# LVDS_IFC_MCX.net
KiCad netlist of a schematic drawn in Altium Designer
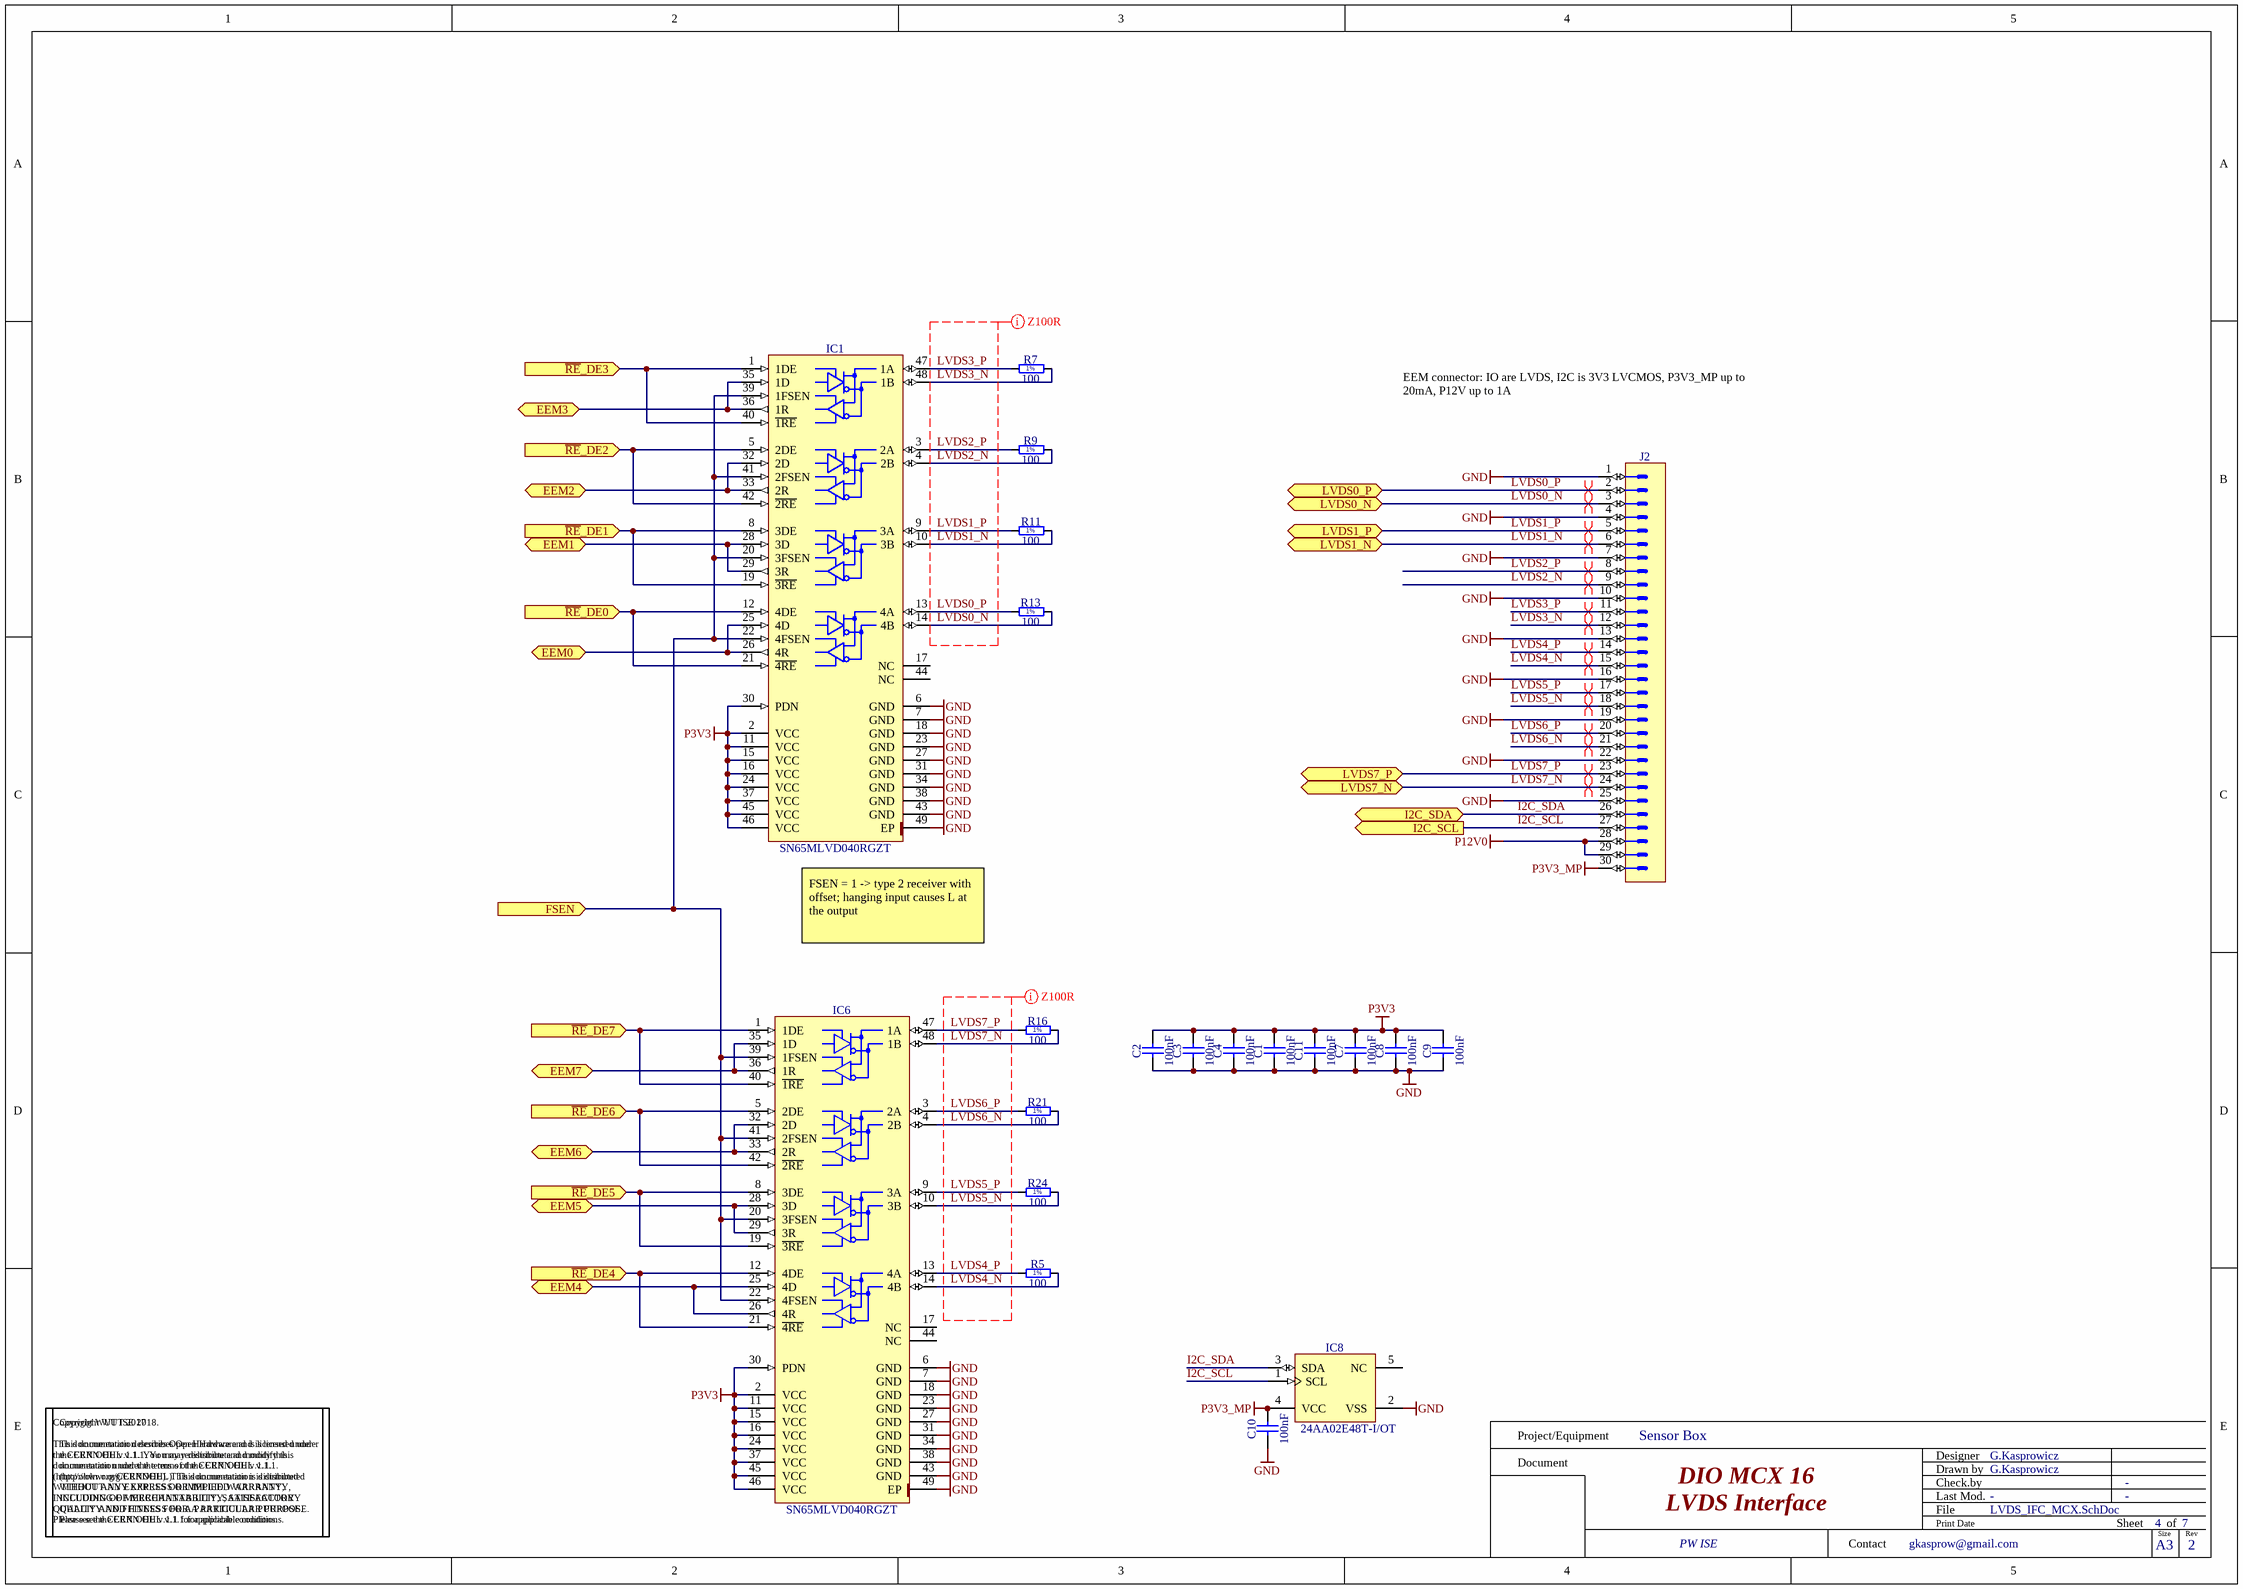
[diagram p0: LVDS_IFC_MCX.SchDoc]

(export (version "E")
  (design (tool "Eeschema 10.0.6"))
  (components
    (comp (ref "C1")
      (value "100nF")
      (footprint "CAPC1005X55N")
      (description "Non-polarised capacitor")
      (fields
        (field (name "PART NUMBER") "CC0402_100NF_16V_10%_X5R")
        (field (name "VOLTAGE") "16V")
        (field (name "AUTHOR") "CERN DEM JLC")
      )
      (libsource (lib "Capacitors") (part "Capacitor - non polarized"))
    )
    (comp (ref "C2")
      (value "100nF")
      (footprint "CAPC1005X55N")
      (description "Non-polarised capacitor")
      (fields
        (field (name "PART NUMBER") "CC0402_100NF_16V_10%_X5R")
        (field (name "VOLTAGE") "16V")
        (field (name "AUTHOR") "CERN DEM JLC")
      )
      (libsource (lib "Capacitors") (part "Capacitor - non polarized"))
    )
    (comp (ref "C3")
      (value "100nF")
      (footprint "CAPC1005X55N")
      (description "Non-polarised capacitor")
      (fields
        (field (name "PART NUMBER") "CC0402_100NF_16V_10%_X5R")
        (field (name "VOLTAGE") "16V")
        (field (name "AUTHOR") "CERN DEM JLC")
      )
      (libsource (lib "Capacitors") (part "Capacitor - non polarized"))
    )
    (comp (ref "C4")
      (value "100nF")
      (footprint "CAPC1005X55N")
      (description "Non-polarised capacitor")
      (fields
        (field (name "PART NUMBER") "CC0402_100NF_16V_10%_X5R")
        (field (name "VOLTAGE") "16V")
        (field (name "AUTHOR") "CERN DEM JLC")
      )
      (libsource (lib "Capacitors") (part "Capacitor - non polarized"))
    )
    (comp (ref "C7")
      (value "100nF")
      (footprint "CAPC1005X55N")
      (description "Non-polarised capacitor")
      (fields
        (field (name "PART NUMBER") "CC0402_100NF_16V_10%_X5R")
        (field (name "VOLTAGE") "16V")
        (field (name "AUTHOR") "CERN DEM JLC")
      )
      (libsource (lib "Capacitors") (part "Capacitor - non polarized"))
    )
    (comp (ref "C8")
      (value "100nF")
      (footprint "CAPC1005X55N")
      (description "Non-polarised capacitor")
      (fields
        (field (name "PART NUMBER") "CC0402_100NF_16V_10%_X5R")
        (field (name "VOLTAGE") "16V")
        (field (name "AUTHOR") "CERN DEM JLC")
      )
      (libsource (lib "Capacitors") (part "Capacitor - non polarized"))
    )
    (comp (ref "C9")
      (value "100nF")
      (footprint "CAPC1005X55N")
      (description "Non-polarised capacitor")
      (fields
        (field (name "PART NUMBER") "CC0402_100NF_16V_10%_X5R")
        (field (name "VOLTAGE") "16V")
        (field (name "AUTHOR") "CERN DEM JLC")
      )
      (libsource (lib "Capacitors") (part "Capacitor - non polarized"))
    )
    (comp (ref "C10")
      (value "100nF")
      (footprint "CAPC1005X55N")
      (description "Non-polarised capacitor")
      (fields
        (field (name "PART NUMBER") "CC0402_100NF_16V_10%_X5R")
        (field (name "VOLTAGE") "16V")
        (field (name "AUTHOR") "CERN DEM JLC")
      )
      (libsource (lib "Capacitors") (part "Capacitor - non polarized"))
    )
    (comp (ref "C11")
      (value "100nF")
      (footprint "CAPC1005X55N")
      (description "Non-polarised capacitor")
      (fields
        (field (name "PART NUMBER") "CC0402_100NF_16V_10%_X5R")
        (field (name "VOLTAGE") "16V")
        (field (name "AUTHOR") "CERN DEM JLC")
      )
      (libsource (lib "Capacitors") (part "Capacitor - non polarized"))
    )
    (comp (ref "IC1")
      (value "SN65MLVD040RGZT")
      (footprint "QFN50P700X700X100-49N-S420")
      (description "4-Channel Half-Duplex M-LVDS Line Transceiver")
      (fields (field (name "MANUFACTURER") "TEXAS INSTRUMENTS") (field (name "AUTHOR") "CERN DEM JLC"))
      (libsource (lib "ICs And Semiconductors") (part "SN65MLVD040"))
    )
    (comp (ref "IC6")
      (value "SN65MLVD040RGZT")
      (footprint "QFN50P700X700X100-49N-S420")
      (description "4-Channel Half-Duplex M-LVDS Line Transceiver")
      (fields (field (name "MANUFACTURER") "TEXAS INSTRUMENTS") (field (name "AUTHOR") "CERN DEM JLC"))
      (libsource (lib "ICs And Semiconductors") (part "SN65MLVD040"))
    )
    (comp (ref "IC8")
      (value "24AA02E48T-I/OT")
      (footprint "SOT95P280X145-5N")
      (description "1.7V-5.5V, 2K I2C Serial EEPROM With EUI-48 Node Identity")
      (fields (field (name "MANUFACTURER") "MICROCHIP TECHNOLOGY") (field (name "AUTHOR") "CERN DEM MR"))
      (libsource (lib "ICs And Semiconductors") (part "24AA02E48T-I/OT"))
    )
    (comp (ref "J2")
      (value "~")
      (footprint "3M_N2530-6002RB")
      (description "Connector 30 Male")
      (fields
        (field (name "PART NUMBER") "3M_N2530-6002RB")
        (field (name "MANUFACTURER") "3M")
        (field (name "AUTHOR") "CERN DEM JLC")
      )
      (libsource (lib "Connectors") (part "Connector 30 Male"))
    )
    (comp (ref "R5")
      (value "100")
      (footprint "RESC1005X40N")
      (description "Resistor - 1%")
      (fields
        (field (name "PART NUMBER") "R0402_100R_1%_0.1W_100PPM")
        (field (name "POWER") "0.1W")
        (field (name "AUTHOR") "CERN DEM JLC")
      )
      (libsource (lib "Resistors") (part "Resistor - 1%"))
    )
    (comp (ref "R7")
      (value "100")
      (footprint "RESC1005X40N")
      (description "Resistor - 1%")
      (fields
        (field (name "PART NUMBER") "R0402_100R_1%_0.1W_100PPM")
        (field (name "POWER") "0.1W")
        (field (name "AUTHOR") "CERN DEM JLC")
      )
      (libsource (lib "Resistors") (part "Resistor - 1%"))
    )
    (comp (ref "R9")
      (value "100")
      (footprint "RESC1005X40N")
      (description "Resistor - 1%")
      (fields
        (field (name "PART NUMBER") "R0402_100R_1%_0.1W_100PPM")
        (field (name "POWER") "0.1W")
        (field (name "AUTHOR") "CERN DEM JLC")
      )
      (libsource (lib "Resistors") (part "Resistor - 1%"))
    )
    (comp (ref "R11")
      (value "100")
      (footprint "RESC1005X40N")
      (description "Resistor - 1%")
      (fields
        (field (name "PART NUMBER") "R0402_100R_1%_0.1W_100PPM")
        (field (name "POWER") "0.1W")
        (field (name "AUTHOR") "CERN DEM JLC")
      )
      (libsource (lib "Resistors") (part "Resistor - 1%"))
    )
    (comp (ref "R13")
      (value "100")
      (footprint "RESC1005X40N")
      (description "Resistor - 1%")
      (fields
        (field (name "PART NUMBER") "R0402_100R_1%_0.1W_100PPM")
        (field (name "POWER") "0.1W")
        (field (name "AUTHOR") "CERN DEM JLC")
      )
      (libsource (lib "Resistors") (part "Resistor - 1%"))
    )
    (comp (ref "R16")
      (value "100")
      (footprint "RESC1005X40N")
      (description "Resistor - 1%")
      (fields
        (field (name "PART NUMBER") "R0402_100R_1%_0.1W_100PPM")
        (field (name "POWER") "0.1W")
        (field (name "AUTHOR") "CERN DEM JLC")
      )
      (libsource (lib "Resistors") (part "Resistor - 1%"))
    )
    (comp (ref "R21")
      (value "100")
      (footprint "RESC1005X40N")
      (description "Resistor - 1%")
      (fields
        (field (name "PART NUMBER") "R0402_100R_1%_0.1W_100PPM")
        (field (name "POWER") "0.1W")
        (field (name "AUTHOR") "CERN DEM JLC")
      )
      (libsource (lib "Resistors") (part "Resistor - 1%"))
    )
    (comp (ref "R24")
      (value "100")
      (footprint "RESC1005X40N")
      (description "Resistor - 1%")
      (fields
        (field (name "PART NUMBER") "R0402_100R_1%_0.1W_100PPM")
        (field (name "POWER") "0.1W")
        (field (name "AUTHOR") "CERN DEM JLC")
      )
      (libsource (lib "Resistors") (part "Resistor - 1%"))
    )
  )
  (nets
    (net (code "1") (name "/EEM0") (class "Default")
      (node (ref "IC1") (pin "25") (pinfunction "4D_25") (pintype "input"))
      (node (ref "IC1") (pin "26") (pinfunction "4R_26") (pintype "output"))
    )
    (net (code "2") (name "/EEM1") (class "Default")
      (node (ref "IC1") (pin "28") (pinfunction "3D_28") (pintype "input"))
      (node (ref "IC1") (pin "29") (pinfunction "3R_29") (pintype "output"))
    )
    (net (code "3") (name "/EEM2") (class "Default")
      (node (ref "IC1") (pin "32") (pinfunction "2D_32") (pintype "input"))
      (node (ref "IC1") (pin "33") (pinfunction "2R_33") (pintype "output"))
    )
    (net (code "4") (name "/EEM3") (class "Default")
      (node (ref "IC1") (pin "35") (pinfunction "1D_35") (pintype "input"))
      (node (ref "IC1") (pin "36") (pinfunction "1R_36") (pintype "output"))
    )
    (net (code "5") (name "/EEM4") (class "Default")
      (node (ref "IC6") (pin "25") (pinfunction "4D_25") (pintype "input"))
      (node (ref "IC6") (pin "26") (pinfunction "4R_26") (pintype "output"))
    )
    (net (code "6") (name "/EEM5") (class "Default")
      (node (ref "IC6") (pin "28") (pinfunction "3D_28") (pintype "input"))
      (node (ref "IC6") (pin "29") (pinfunction "3R_29") (pintype "output"))
    )
    (net (code "7") (name "/EEM6") (class "Default")
      (node (ref "IC6") (pin "32") (pinfunction "2D_32") (pintype "input"))
      (node (ref "IC6") (pin "33") (pinfunction "2R_33") (pintype "output"))
    )
    (net (code "8") (name "/EEM7") (class "Default")
      (node (ref "IC6") (pin "35") (pinfunction "1D_35") (pintype "input"))
      (node (ref "IC6") (pin "36") (pinfunction "1R_36") (pintype "output"))
    )
    (net (code "9") (name "/FSEN") (class "Default")
      (node (ref "IC1") (pin "20") (pinfunction "3FSEN_20") (pintype "input"))
      (node (ref "IC1") (pin "22") (pinfunction "4FSEN_22") (pintype "input"))
      (node (ref "IC1") (pin "39") (pinfunction "1FSEN_39") (pintype "input"))
      (node (ref "IC1") (pin "41") (pinfunction "2FSEN_41") (pintype "input"))
      (node (ref "IC6") (pin "20") (pinfunction "3FSEN_20") (pintype "input"))
      (node (ref "IC6") (pin "22") (pinfunction "4FSEN_22") (pintype "input"))
      (node (ref "IC6") (pin "39") (pinfunction "1FSEN_39") (pintype "input"))
      (node (ref "IC6") (pin "41") (pinfunction "2FSEN_41") (pintype "input"))
    )
    (net (code "10") (name "/I2C_SCL") (class "Default")
      (node (ref "IC8") (pin "1") (pinfunction "SCL_1") (pintype "input"))
      (node (ref "J2") (pin "27") (pinfunction "27_27") (pintype "bidirectional"))
    )
    (net (code "11") (name "/I2C_SDA") (class "Default")
      (node (ref "IC8") (pin "3") (pinfunction "SDA_3") (pintype "bidirectional"))
      (node (ref "J2") (pin "26") (pinfunction "26_26") (pintype "bidirectional"))
    )
    (net (code "12") (name "/LVDS0_N") (class "Default")
      (node (ref "IC1") (pin "14") (pinfunction "4B_14") (pintype "bidirectional"))
      (node (ref "J2") (pin "3") (pinfunction "3_3") (pintype "bidirectional"))
      (node (ref "R13") (pin "2") (pinfunction "2_2") (pintype "passive"))
    )
    (net (code "13") (name "/LVDS0_P") (class "Default")
      (node (ref "IC1") (pin "13") (pinfunction "4A_13") (pintype "bidirectional"))
      (node (ref "J2") (pin "2") (pinfunction "2_2") (pintype "bidirectional"))
      (node (ref "R13") (pin "1") (pinfunction "1_1") (pintype "passive"))
    )
    (net (code "14") (name "/LVDS1_N") (class "Default")
      (node (ref "IC1") (pin "10") (pinfunction "3B_10") (pintype "bidirectional"))
      (node (ref "J2") (pin "6") (pinfunction "6_6") (pintype "bidirectional"))
      (node (ref "R11") (pin "2") (pinfunction "2_2") (pintype "passive"))
    )
    (net (code "15") (name "/LVDS1_P") (class "Default")
      (node (ref "IC1") (pin "9") (pinfunction "3A_9") (pintype "bidirectional"))
      (node (ref "J2") (pin "5") (pinfunction "5_5") (pintype "bidirectional"))
      (node (ref "R11") (pin "1") (pinfunction "1_1") (pintype "passive"))
    )
    (net (code "16") (name "/LVDS2_N") (class "Default")
      (node (ref "IC1") (pin "4") (pinfunction "2B_4") (pintype "bidirectional"))
      (node (ref "J2") (pin "9") (pinfunction "9_9") (pintype "bidirectional"))
      (node (ref "R9") (pin "2") (pinfunction "2_2") (pintype "passive"))
    )
    (net (code "17") (name "/LVDS2_P") (class "Default")
      (node (ref "IC1") (pin "3") (pinfunction "2A_3") (pintype "bidirectional"))
      (node (ref "J2") (pin "8") (pinfunction "8_8") (pintype "bidirectional"))
      (node (ref "R9") (pin "1") (pinfunction "1_1") (pintype "passive"))
    )
    (net (code "18") (name "/LVDS3_N") (class "Default")
      (node (ref "IC1") (pin "48") (pinfunction "1B_48") (pintype "bidirectional"))
      (node (ref "J2") (pin "12") (pinfunction "12_12") (pintype "bidirectional"))
      (node (ref "R7") (pin "2") (pinfunction "2_2") (pintype "passive"))
    )
    (net (code "19") (name "/LVDS3_P") (class "Default")
      (node (ref "IC1") (pin "47") (pinfunction "1A_47") (pintype "bidirectional"))
      (node (ref "J2") (pin "11") (pinfunction "11_11") (pintype "bidirectional"))
      (node (ref "R7") (pin "1") (pinfunction "1_1") (pintype "passive"))
    )
    (net (code "20") (name "/LVDS4_N") (class "Default")
      (node (ref "IC6") (pin "14") (pinfunction "4B_14") (pintype "bidirectional"))
      (node (ref "J2") (pin "15") (pinfunction "15_15") (pintype "bidirectional"))
      (node (ref "R5") (pin "2") (pinfunction "2_2") (pintype "passive"))
    )
    (net (code "21") (name "/LVDS4_P") (class "Default")
      (node (ref "IC6") (pin "13") (pinfunction "4A_13") (pintype "bidirectional"))
      (node (ref "J2") (pin "14") (pinfunction "14_14") (pintype "bidirectional"))
      (node (ref "R5") (pin "1") (pinfunction "1_1") (pintype "passive"))
    )
    (net (code "22") (name "/LVDS5_N") (class "Default")
      (node (ref "IC6") (pin "10") (pinfunction "3B_10") (pintype "bidirectional"))
      (node (ref "J2") (pin "18") (pinfunction "18_18") (pintype "bidirectional"))
      (node (ref "R24") (pin "2") (pinfunction "2_2") (pintype "passive"))
    )
    (net (code "23") (name "/LVDS5_P") (class "Default")
      (node (ref "IC6") (pin "9") (pinfunction "3A_9") (pintype "bidirectional"))
      (node (ref "J2") (pin "17") (pinfunction "17_17") (pintype "bidirectional"))
      (node (ref "R24") (pin "1") (pinfunction "1_1") (pintype "passive"))
    )
    (net (code "24") (name "/LVDS6_N") (class "Default")
      (node (ref "IC6") (pin "4") (pinfunction "2B_4") (pintype "bidirectional"))
      (node (ref "J2") (pin "21") (pinfunction "21_21") (pintype "bidirectional"))
      (node (ref "R21") (pin "2") (pinfunction "2_2") (pintype "passive"))
    )
    (net (code "25") (name "/LVDS6_P") (class "Default")
      (node (ref "IC6") (pin "3") (pinfunction "2A_3") (pintype "bidirectional"))
      (node (ref "J2") (pin "20") (pinfunction "20_20") (pintype "bidirectional"))
      (node (ref "R21") (pin "1") (pinfunction "1_1") (pintype "passive"))
    )
    (net (code "26") (name "/LVDS7_N") (class "Default")
      (node (ref "IC6") (pin "48") (pinfunction "1B_48") (pintype "bidirectional"))
      (node (ref "J2") (pin "24") (pinfunction "24_24") (pintype "bidirectional"))
      (node (ref "R16") (pin "2") (pinfunction "2_2") (pintype "passive"))
    )
    (net (code "27") (name "/LVDS7_P") (class "Default")
      (node (ref "IC6") (pin "47") (pinfunction "1A_47") (pintype "bidirectional"))
      (node (ref "J2") (pin "23") (pinfunction "23_23") (pintype "bidirectional"))
      (node (ref "R16") (pin "1") (pinfunction "1_1") (pintype "passive"))
    )
    (net (code "28") (name "/~{RE}_DE0") (class "Default")
      (node (ref "IC1") (pin "12") (pinfunction "4DE_12") (pintype "input"))
      (node (ref "IC1") (pin "21") (pinfunction "~{4RE}_21") (pintype "input"))
    )
    (net (code "29") (name "/~{RE}_DE1") (class "Default")
      (node (ref "IC1") (pin "19") (pinfunction "~{3RE}_19") (pintype "input"))
      (node (ref "IC1") (pin "8") (pinfunction "3DE_8") (pintype "input"))
    )
    (net (code "30") (name "/~{RE}_DE2") (class "Default")
      (node (ref "IC1") (pin "42") (pinfunction "~{2RE}_42") (pintype "input"))
      (node (ref "IC1") (pin "5") (pinfunction "2DE_5") (pintype "input"))
    )
    (net (code "31") (name "/~{RE}_DE3") (class "Default")
      (node (ref "IC1") (pin "1") (pinfunction "1DE_1") (pintype "input"))
      (node (ref "IC1") (pin "40") (pinfunction "~{1RE}_40") (pintype "input"))
    )
    (net (code "32") (name "/~{RE}_DE4") (class "Default")
      (node (ref "IC6") (pin "12") (pinfunction "4DE_12") (pintype "input"))
      (node (ref "IC6") (pin "21") (pinfunction "~{4RE}_21") (pintype "input"))
    )
    (net (code "33") (name "/~{RE}_DE5") (class "Default")
      (node (ref "IC6") (pin "19") (pinfunction "~{3RE}_19") (pintype "input"))
      (node (ref "IC6") (pin "8") (pinfunction "3DE_8") (pintype "input"))
    )
    (net (code "34") (name "/~{RE}_DE6") (class "Default")
      (node (ref "IC6") (pin "42") (pinfunction "~{2RE}_42") (pintype "input"))
      (node (ref "IC6") (pin "5") (pinfunction "2DE_5") (pintype "input"))
    )
    (net (code "35") (name "/~{RE}_DE7") (class "Default")
      (node (ref "IC6") (pin "1") (pinfunction "1DE_1") (pintype "input"))
      (node (ref "IC6") (pin "40") (pinfunction "~{1RE}_40") (pintype "input"))
    )
    (net (code "36") (name "GND") (class "Default")
      (node (ref "C1") (pin "1") (pinfunction "1_1") (pintype "passive"))
      (node (ref "C10") (pin "1") (pinfunction "1_1") (pintype "passive"))
      (node (ref "C11") (pin "1") (pinfunction "1_1") (pintype "passive"))
      (node (ref "C2") (pin "1") (pinfunction "1_1") (pintype "passive"))
      (node (ref "C3") (pin "1") (pinfunction "1_1") (pintype "passive"))
      (node (ref "C4") (pin "1") (pinfunction "1_1") (pintype "passive"))
      (node (ref "C7") (pin "1") (pinfunction "1_1") (pintype "passive"))
      (node (ref "C8") (pin "1") (pinfunction "1_1") (pintype "passive"))
      (node (ref "C9") (pin "1") (pinfunction "1_1") (pintype "passive"))
      (node (ref "IC1") (pin "18") (pinfunction "GND_18") (pintype "power_in"))
      (node (ref "IC1") (pin "23") (pinfunction "GND_23") (pintype "power_in"))
      (node (ref "IC1") (pin "27") (pinfunction "GND_27") (pintype "power_in"))
      (node (ref "IC1") (pin "31") (pinfunction "GND_31") (pintype "power_in"))
      (node (ref "IC1") (pin "34") (pinfunction "GND_34") (pintype "power_in"))
      (node (ref "IC1") (pin "38") (pinfunction "GND_38") (pintype "power_in"))
      (node (ref "IC1") (pin "43") (pinfunction "GND_43") (pintype "power_in"))
      (node (ref "IC1") (pin "49") (pinfunction "EP_49") (pintype "power_in"))
      (node (ref "IC1") (pin "6") (pinfunction "GND_6") (pintype "power_in"))
      (node (ref "IC1") (pin "7") (pinfunction "GND_7") (pintype "power_in"))
      (node (ref "IC6") (pin "18") (pinfunction "GND_18") (pintype "power_in"))
      (node (ref "IC6") (pin "23") (pinfunction "GND_23") (pintype "power_in"))
      (node (ref "IC6") (pin "27") (pinfunction "GND_27") (pintype "power_in"))
      (node (ref "IC6") (pin "31") (pinfunction "GND_31") (pintype "power_in"))
      (node (ref "IC6") (pin "34") (pinfunction "GND_34") (pintype "power_in"))
      (node (ref "IC6") (pin "38") (pinfunction "GND_38") (pintype "power_in"))
      (node (ref "IC6") (pin "43") (pinfunction "GND_43") (pintype "power_in"))
      (node (ref "IC6") (pin "49") (pinfunction "EP_49") (pintype "power_in"))
      (node (ref "IC6") (pin "6") (pinfunction "GND_6") (pintype "power_in"))
      (node (ref "IC6") (pin "7") (pinfunction "GND_7") (pintype "power_in"))
      (node (ref "IC8") (pin "2") (pinfunction "VSS_2") (pintype "power_in"))
      (node (ref "J2") (pin "1") (pinfunction "1_1") (pintype "bidirectional"))
      (node (ref "J2") (pin "10") (pinfunction "10_10") (pintype "bidirectional"))
      (node (ref "J2") (pin "13") (pinfunction "13_13") (pintype "bidirectional"))
      (node (ref "J2") (pin "16") (pinfunction "16_16") (pintype "bidirectional"))
      (node (ref "J2") (pin "19") (pinfunction "19_19") (pintype "bidirectional"))
      (node (ref "J2") (pin "22") (pinfunction "22_22") (pintype "bidirectional"))
      (node (ref "J2") (pin "25") (pinfunction "25_25") (pintype "bidirectional"))
      (node (ref "J2") (pin "4") (pinfunction "4_4") (pintype "bidirectional"))
      (node (ref "J2") (pin "7") (pinfunction "7_7") (pintype "bidirectional"))
    )
    (net (code "37") (name "P3V3") (class "Default")
      (node (ref "C1") (pin "2") (pinfunction "2_2") (pintype "passive"))
      (node (ref "C11") (pin "2") (pinfunction "2_2") (pintype "passive"))
      (node (ref "C2") (pin "2") (pinfunction "2_2") (pintype "passive"))
      (node (ref "C3") (pin "2") (pinfunction "2_2") (pintype "passive"))
      (node (ref "C4") (pin "2") (pinfunction "2_2") (pintype "passive"))
      (node (ref "C7") (pin "2") (pinfunction "2_2") (pintype "passive"))
      (node (ref "C8") (pin "2") (pinfunction "2_2") (pintype "passive"))
      (node (ref "C9") (pin "2") (pinfunction "2_2") (pintype "passive"))
      (node (ref "IC1") (pin "11") (pinfunction "VCC_11") (pintype "power_in"))
      (node (ref "IC1") (pin "15") (pinfunction "VCC_15") (pintype "power_in"))
      (node (ref "IC1") (pin "16") (pinfunction "VCC_16") (pintype "power_in"))
      (node (ref "IC1") (pin "2") (pinfunction "VCC_2") (pintype "power_in"))
      (node (ref "IC1") (pin "24") (pinfunction "VCC_24") (pintype "power_in"))
      (node (ref "IC1") (pin "30") (pinfunction "PDN_30") (pintype "input"))
      (node (ref "IC1") (pin "37") (pinfunction "VCC_37") (pintype "power_in"))
      (node (ref "IC1") (pin "45") (pinfunction "VCC_45") (pintype "power_in"))
      (node (ref "IC1") (pin "46") (pinfunction "VCC_46") (pintype "power_in"))
      (node (ref "IC6") (pin "11") (pinfunction "VCC_11") (pintype "power_in"))
      (node (ref "IC6") (pin "15") (pinfunction "VCC_15") (pintype "power_in"))
      (node (ref "IC6") (pin "16") (pinfunction "VCC_16") (pintype "power_in"))
      (node (ref "IC6") (pin "2") (pinfunction "VCC_2") (pintype "power_in"))
      (node (ref "IC6") (pin "24") (pinfunction "VCC_24") (pintype "power_in"))
      (node (ref "IC6") (pin "30") (pinfunction "PDN_30") (pintype "input"))
      (node (ref "IC6") (pin "37") (pinfunction "VCC_37") (pintype "power_in"))
      (node (ref "IC6") (pin "45") (pinfunction "VCC_45") (pintype "power_in"))
      (node (ref "IC6") (pin "46") (pinfunction "VCC_46") (pintype "power_in"))
    )
    (net (code "38") (name "P3V3_MP") (class "Default")
      (node (ref "C10") (pin "2") (pinfunction "2_2") (pintype "passive"))
      (node (ref "IC8") (pin "4") (pinfunction "VCC_4") (pintype "power_in"))
      (node (ref "J2") (pin "30") (pinfunction "30_30") (pintype "bidirectional"))
    )
    (net (code "39") (name "P12V0") (class "Default")
      (node (ref "J2") (pin "28") (pinfunction "28_28") (pintype "bidirectional"))
      (node (ref "J2") (pin "29") (pinfunction "29_29") (pintype "bidirectional"))
    )
    (net (code "40") (name "unconnected-(IC1-NC-Pad17)") (class "Default")
      (node (ref "IC1") (pin "17") (pinfunction "NC_17") (pintype "passive"))
    )
    (net (code "41") (name "unconnected-(IC1-NC-Pad44)") (class "Default")
      (node (ref "IC1") (pin "44") (pinfunction "NC_44") (pintype "passive"))
    )
    (net (code "42") (name "unconnected-(IC6-NC-Pad17)") (class "Default")
      (node (ref "IC6") (pin "17") (pinfunction "NC_17") (pintype "passive"))
    )
    (net (code "43") (name "unconnected-(IC6-NC-Pad44)") (class "Default")
      (node (ref "IC6") (pin "44") (pinfunction "NC_44") (pintype "passive"))
    )
    (net (code "44") (name "unconnected-(IC8-NC-Pad5)") (class "Default")
      (node (ref "IC8") (pin "5") (pinfunction "NC_5") (pintype "passive"))
    )
  )
)
